# lab2_task2.net
KiCad netlist of a schematic drawn in EAGLE
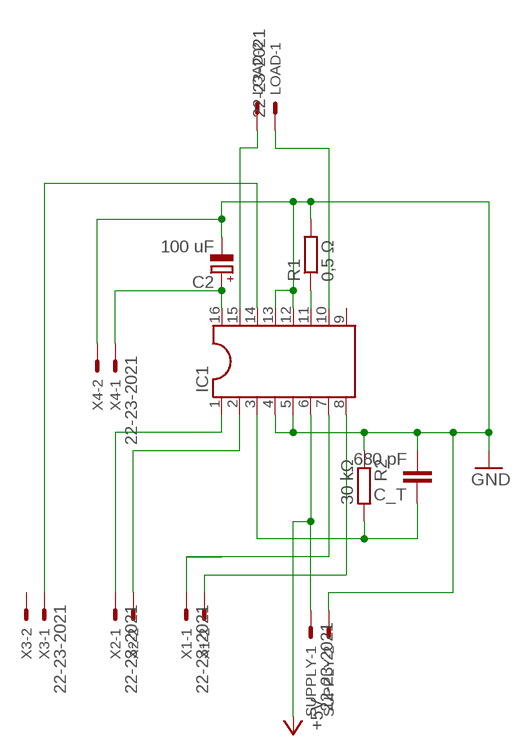
[diagram p0: schematic, sheet 1]

(export (version "E")
  (design (tool "Eeschema 10.0.6"))
  (components
    (comp (ref "C2")
      (value "100 uF")
      (footprint "eagle-import:E5-13")
      (libsource (lib "eagle-import") (part "CPOL-EUE5-13"))
    )
    (comp (ref "C_T")
      (value "680 pF")
      (footprint "eagle-import:C050-035X075")
      (libsource (lib "eagle-import") (part "C-EU050-035X075"))
    )
    (comp (ref "IC1")
      (value "DIL16")
      (footprint "eagle-import:DIL16")
      (libsource (lib "eagle-import") (part "DIL16"))
    )
    (comp (ref "LOAD")
      (value "22-23-2021")
      (footprint "eagle-import:22-23-2021")
      (fields (field (name "MF") "MOLEX"))
      (libsource (lib "eagle-import") (part "22-23-2021"))
    )
    (comp (ref "R1")
      (value "0,5 Ω")
      (footprint "eagle-import:0207_10")
      (libsource (lib "eagle-import") (part "R-EU_0207/10"))
    )
    (comp (ref "R2")
      (value "30 kΩ")
      (footprint "eagle-import:0207_10")
      (libsource (lib "eagle-import") (part "R-EU_0207/10"))
    )
    (comp (ref "SUPPLY")
      (value "22-23-2021")
      (footprint "eagle-import:22-23-2021")
      (fields (field (name "MF") "MOLEX"))
      (libsource (lib "eagle-import") (part "22-23-2021"))
    )
    (comp (ref "X1")
      (value "22-23-2021")
      (footprint "eagle-import:22-23-2021")
      (fields (field (name "MF") "MOLEX"))
      (libsource (lib "eagle-import") (part "22-23-2021"))
    )
    (comp (ref "X2")
      (value "22-23-2021")
      (footprint "eagle-import:22-23-2021")
      (fields (field (name "MF") "MOLEX"))
      (libsource (lib "eagle-import") (part "22-23-2021"))
    )
    (comp (ref "X3")
      (value "22-23-2021")
      (footprint "eagle-import:22-23-2021")
      (fields (field (name "MF") "MOLEX"))
      (libsource (lib "eagle-import") (part "22-23-2021"))
    )
    (comp (ref "X4")
      (value "22-23-2021")
      (footprint "eagle-import:22-23-2021")
      (fields (field (name "MF") "MOLEX"))
      (libsource (lib "eagle-import") (part "22-23-2021"))
    )
  )
  (nets
    (net (code "1") (name "+5V") (class "Default")
      (node (ref "IC1") (pin "6") (pinfunction "6_6") (pintype "passive"))
      (node (ref "SUPPLY") (pin "1") (pinfunction "S_1") (pintype "passive"))
    )
    (net (code "2") (name "GND") (class "Default")
      (node (ref "C2") (pin "-") (pinfunction "-_-") (pintype "passive"))
      (node (ref "C_T") (pin "2") (pinfunction "2_2") (pintype "passive"))
      (node (ref "IC1") (pin "12") (pinfunction "12_12") (pintype "passive"))
      (node (ref "IC1") (pin "13") (pinfunction "13_13") (pintype "passive"))
      (node (ref "IC1") (pin "4") (pinfunction "4_4") (pintype "passive"))
      (node (ref "IC1") (pin "5") (pinfunction "5_5") (pintype "passive"))
      (node (ref "R1") (pin "2") (pinfunction "2_2") (pintype "passive"))
      (node (ref "R2") (pin "1") (pinfunction "1_1") (pintype "passive"))
      (node (ref "SUPPLY") (pin "2") (pinfunction "S_2") (pintype "passive"))
      (node (ref "X4") (pin "2") (pinfunction "S_2") (pintype "passive"))
    )
    (net (code "3") (name "Net-(C_T-Pad1)") (class "Default")
      (node (ref "C_T") (pin "1") (pinfunction "1_1") (pintype "passive"))
      (node (ref "IC1") (pin "3") (pinfunction "3_3") (pintype "passive"))
      (node (ref "R2") (pin "2") (pinfunction "2_2") (pintype "passive"))
    )
    (net (code "4") (name "Net-(IC1-Pad11)") (class "Default")
      (node (ref "IC1") (pin "11") (pinfunction "11_11") (pintype "passive"))
      (node (ref "R1") (pin "1") (pinfunction "1_1") (pintype "passive"))
    )
    (net (code "5") (name "Net-(LOADA-S)") (class "Default")
      (node (ref "IC1") (pin "10") (pinfunction "10_10") (pintype "passive"))
      (node (ref "LOAD") (pin "1") (pinfunction "S_1") (pintype "passive"))
    )
    (net (code "6") (name "Net-(LOADB-S)") (class "Default")
      (node (ref "IC1") (pin "15") (pinfunction "15_15") (pintype "passive"))
      (node (ref "LOAD") (pin "2") (pinfunction "S_2") (pintype "passive"))
    )
    (net (code "7") (name "Net-(X1A-S)") (class "Default")
      (node (ref "IC1") (pin "7") (pinfunction "7_7") (pintype "passive"))
      (node (ref "X1") (pin "1") (pinfunction "S_1") (pintype "passive"))
    )
    (net (code "8") (name "Net-(X1B-S)") (class "Default")
      (node (ref "IC1") (pin "8") (pinfunction "8_8") (pintype "passive"))
      (node (ref "X1") (pin "2") (pinfunction "S_2") (pintype "passive"))
    )
    (net (code "9") (name "Net-(X2A-S)") (class "Default")
      (node (ref "IC1") (pin "1") (pinfunction "1_1") (pintype "passive"))
      (node (ref "X2") (pin "1") (pinfunction "S_1") (pintype "passive"))
    )
    (net (code "10") (name "Net-(X2B-S)") (class "Default")
      (node (ref "IC1") (pin "2") (pinfunction "2_2") (pintype "passive"))
      (node (ref "X2") (pin "2") (pinfunction "S_2") (pintype "passive"))
    )
    (net (code "11") (name "Net-(X3A-S)") (class "Default")
      (node (ref "IC1") (pin "14") (pinfunction "14_14") (pintype "passive"))
      (node (ref "X3") (pin "1") (pinfunction "S_1") (pintype "passive"))
    )
    (net (code "12") (name "Net-(X4A-S)") (class "Default")
      (node (ref "C2") (pin "+") (pinfunction "+_+") (pintype "passive"))
      (node (ref "IC1") (pin "16") (pinfunction "16_16") (pintype "passive"))
      (node (ref "X4") (pin "1") (pinfunction "S_1") (pintype "passive"))
    )
    (net (code "13") (name "unconnected-(IC1-Pad9)") (class "Default")
      (node (ref "IC1") (pin "9") (pinfunction "9_9") (pintype "passive"))
    )
    (net (code "14") (name "unconnected-(X3B-S-Pad2)") (class "Default")
      (node (ref "X3") (pin "2") (pinfunction "S_2") (pintype "passive"))
    )
  )
)
